# 3_classyTKL_mcu.net
KiCad netlist of a schematic drawn in Altium Designer
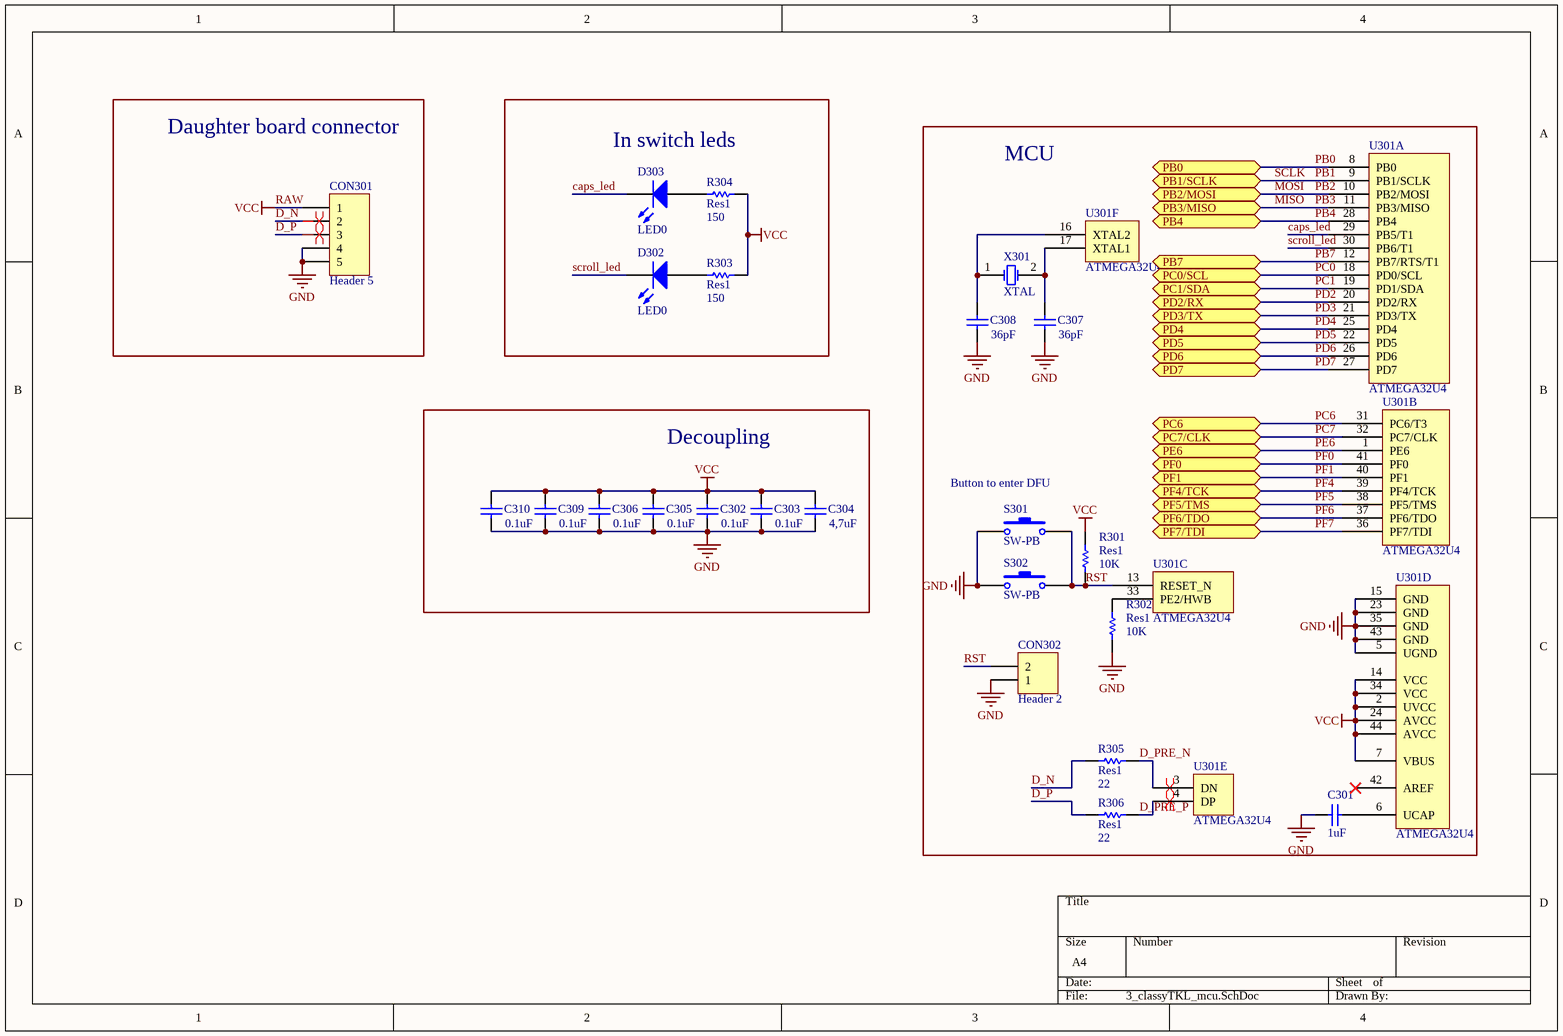
[diagram p0: 3_classyTKL_mcu.SchDoc]

(export (version "E")
  (design (tool "Eeschema 10.0.6"))
  (components
    (comp (ref "C301")
      (value "1uF")
      (footprint "C0603[1608]")
      (description "Capacitor")
      (fields (field (name "MFG") "KEMET") (field (name "LCSC PART #") "C15849"))
      (libsource (lib "Miscellaneous Devices") (part "Cap"))
    )
    (comp (ref "C302")
      (value "0.1uF")
      (footprint "C0603[1608]")
      (description "Capacitor")
      (fields (field (name "MFG") "KEMET") (field (name "LCSC PART #") "C14663"))
      (libsource (lib "Miscellaneous Devices") (part "Cap"))
    )
    (comp (ref "C303")
      (value "0.1uF")
      (footprint "C0603[1608]")
      (description "Capacitor")
      (fields (field (name "MFG") "KEMET") (field (name "LCSC PART #") "C14663"))
      (libsource (lib "Miscellaneous Devices") (part "Cap"))
    )
    (comp (ref "C304")
      (value "4,7uF")
      (footprint "C1206[3216]")
      (description "Capacitor")
      (fields (field (name "MFG") "KEMET") (field (name "LCSC PART #") "C29823"))
      (libsource (lib "Miscellaneous Devices") (part "Cap"))
    )
    (comp (ref "C305")
      (value "0.1uF")
      (footprint "C0603[1608]")
      (description "Capacitor")
      (fields (field (name "MFG") "KEMET") (field (name "LCSC PART #") "C14663"))
      (libsource (lib "Miscellaneous Devices") (part "Cap"))
    )
    (comp (ref "C306")
      (value "0.1uF")
      (footprint "C0603[1608]")
      (description "Capacitor")
      (fields (field (name "MFG") "KEMET") (field (name "LCSC PART #") "C14663"))
      (libsource (lib "Miscellaneous Devices") (part "Cap"))
    )
    (comp (ref "C307")
      (value "36pF")
      (footprint "C0603[1608]")
      (description "Capacitor")
      (fields (field (name "MFG") "KEMET") (field (name "LCSC PART #") "C159790"))
      (libsource (lib "Miscellaneous Devices") (part "Cap"))
    )
    (comp (ref "C308")
      (value "36pF")
      (footprint "C0603[1608]")
      (description "Capacitor")
      (fields (field (name "MFG") "KEMET") (field (name "LCSC PART #") "C159790"))
      (libsource (lib "Miscellaneous Devices") (part "Cap"))
    )
    (comp (ref "C309")
      (value "0.1uF")
      (footprint "C0603[1608]")
      (description "Capacitor")
      (fields (field (name "MFG") "KEMET") (field (name "LCSC PART #") "C14663"))
      (libsource (lib "Miscellaneous Devices") (part "Cap"))
    )
    (comp (ref "C310")
      (value "0.1uF")
      (footprint "C0603[1608]")
      (description "Capacitor")
      (fields (field (name "MFG") "KEMET") (field (name "LCSC PART #") "C14663"))
      (libsource (lib "Miscellaneous Devices") (part "Cap"))
    )
    (comp (ref "CON301")
      (value "Header 5")
      (footprint "JST SM04B-SRSS-TB")
      (description "JST for USB daughter board")
      (fields (field (name "MFG") "JST Sales America Inc.") (field (name "LCSC PART #") "C160404"))
      (libsource (lib "Miscellaneous Connectors") (part "Header 5"))
    )
    (comp (ref "CON302")
      (value "Header 2")
      (footprint "HDR1X2")
      (description "Header, 2-Pin")
      (libsource (lib "Miscellaneous Connectors") (part "Header 2"))
    )
    (comp (ref "D302")
      (value "LED0")
      (footprint "MX-switch - LED")
      (description "Typical INFRARED GaAs LED")
      (libsource (lib "Miscellaneous Devices") (part "LED0"))
    )
    (comp (ref "D303")
      (value "LED0")
      (footprint "MX-switch - CAPS - LED NO SWITCH")
      (description "Typical INFRARED GaAs LED")
      (libsource (lib "Miscellaneous Devices") (part "LED0"))
    )
    (comp (ref "R301")
      (value "Res1")
      (footprint "R0603[1608]")
      (description "Resistor")
      (fields
        (field (name "ALTIUM_VALUE") "10K")
        (field (name "MFG") "Panasonic Electronic Components")
        (field (name "LCSC PART #") "C25804")
      )
      (libsource (lib "Miscellaneous Devices") (part "Res1"))
    )
    (comp (ref "R302")
      (value "Res1")
      (footprint "R0603[1608]")
      (description "Resistor")
      (fields
        (field (name "ALTIUM_VALUE") "10K")
        (field (name "MFG") "Panasonic Electronic Components")
        (field (name "LCSC PART #") "C25804")
      )
      (libsource (lib "Miscellaneous Devices") (part "Res1"))
    )
    (comp (ref "R303")
      (value "Res1")
      (footprint "R0603[1608] - THT")
      (description "Resistor")
      (fields (field (name "ALTIUM_VALUE") "150"))
      (libsource (lib "Miscellaneous Devices") (part "Res1"))
    )
    (comp (ref "R304")
      (value "Res1")
      (footprint "R0603[1608] - THT")
      (description "Resistor")
      (fields (field (name "ALTIUM_VALUE") "150"))
      (libsource (lib "Miscellaneous Devices") (part "Res1"))
    )
    (comp (ref "R305")
      (value "Res1")
      (footprint "R0603[1608]")
      (description "Resistor")
      (fields
        (field (name "ALTIUM_VALUE") "22")
        (field (name "MFG") "Panasonic Electronic Components")
        (field (name "LCSC PART #") "C23345")
      )
      (libsource (lib "Miscellaneous Devices") (part "Res1"))
    )
    (comp (ref "R306")
      (value "Res1")
      (footprint "R0603[1608]")
      (description "Resistor")
      (fields
        (field (name "ALTIUM_VALUE") "22")
        (field (name "MFG") "Panasonic Electronic Components")
        (field (name "LCSC PART #") "C23345")
      )
      (libsource (lib "Miscellaneous Devices") (part "Res1"))
    )
    (comp (ref "S301")
      (value "SW-PB")
      (footprint "Combo switch")
      (description "Switch")
      (fields (field (name "MFG") "C&K") (field (name "LCSC PART #") "C318888"))
      (libsource (lib "Miscellaneous Devices") (part "SW-PB"))
    )
    (comp (ref "S302")
      (value "SW-PB")
      (footprint "Combo switch")
      (description "Switch")
      (fields (field (name "MFG") "C&K") (field (name "LCSC PART #") "C318888"))
      (libsource (lib "Miscellaneous Devices") (part "SW-PB"))
    )
    (comp (ref "U301")
      (value "ATMEGA32U4")
      (footprint "ATMEGA32U4-COMBO")
      (description "MCU")
      (fields
        (field (name "LCSC PART #") "C45874")
        (field (name "MFG") "Microchip Technology")
        (field (name "MRF.PART") "ATMEGA32U4-MUR")
      )
      (libsource (lib "") (part "ATMEGA32U4_1"))
    )
    (comp (ref "X301")
      (value "XTAL")
      (footprint "CTS 445-series crystal")
      (description "Crystal Oscillator")
      (fields (field (name "LCSC PART #") "C112572") (field (name "MRF.PART") "X503216MSB2GI"))
      (libsource (lib "Miscellaneous Devices") (part "XTAL"))
    )
  )
  (nets
    (net (code "1") (name "/D_N") (class "Default")
      (node (ref "CON301") (pin "2") (pinfunction "2_2") (pintype "passive"))
      (node (ref "R305") (pin "2") (pinfunction "2_2") (pintype "passive"))
    )
    (net (code "2") (name "/D_P") (class "Default")
      (node (ref "CON301") (pin "3") (pinfunction "3_3") (pintype "passive"))
      (node (ref "R306") (pin "2") (pinfunction "2_2") (pintype "passive"))
    )
    (net (code "3") (name "/D_PRE_N") (class "Default")
      (node (ref "R305") (pin "1") (pinfunction "1_1") (pintype "passive"))
      (node (ref "U301") (pin "3") (pinfunction "DN_3") (pintype "passive"))
    )
    (net (code "4") (name "/D_PRE_P") (class "Default")
      (node (ref "R306") (pin "1") (pinfunction "1_1") (pintype "passive"))
      (node (ref "U301") (pin "4") (pinfunction "DP_4") (pintype "passive"))
    )
    (net (code "5") (name "/MISO") (class "Default")
      (node (ref "U301") (pin "11") (pinfunction "PB3/MISO_11") (pintype "passive"))
    )
    (net (code "6") (name "/MOSI") (class "Default")
      (node (ref "U301") (pin "10") (pinfunction "PB2/MOSI_10") (pintype "passive"))
    )
    (net (code "7") (name "/PB0") (class "Default")
      (node (ref "U301") (pin "8") (pinfunction "PB0_8") (pintype "passive"))
    )
    (net (code "8") (name "/PB1") (class "Default")
      (node (ref "U301") (pin "9") (pinfunction "PB1/SCLK_9") (pintype "passive"))
    )
    (net (code "9") (name "/PB4") (class "Default")
      (node (ref "U301") (pin "28") (pinfunction "PB4_28") (pintype "passive"))
    )
    (net (code "10") (name "/PB7") (class "Default")
      (node (ref "U301") (pin "12") (pinfunction "PB7/RTS/T1_12") (pintype "passive"))
    )
    (net (code "11") (name "/PC0") (class "Default")
      (node (ref "U301") (pin "18") (pinfunction "PD0/SCL_18") (pintype "passive"))
    )
    (net (code "12") (name "/PC1") (class "Default")
      (node (ref "U301") (pin "19") (pinfunction "PD1/SDA_19") (pintype "passive"))
    )
    (net (code "13") (name "/PC6") (class "Default")
      (node (ref "U301") (pin "31") (pinfunction "PC6/T3_31") (pintype "passive"))
    )
    (net (code "14") (name "/PC7") (class "Default")
      (node (ref "U301") (pin "32") (pinfunction "PC7/CLK_32") (pintype "passive"))
    )
    (net (code "15") (name "/PD2") (class "Default")
      (node (ref "U301") (pin "20") (pinfunction "PD2/RX_20") (pintype "passive"))
    )
    (net (code "16") (name "/PD3") (class "Default")
      (node (ref "U301") (pin "21") (pinfunction "PD3/TX_21") (pintype "passive"))
    )
    (net (code "17") (name "/PD4") (class "Default")
      (node (ref "U301") (pin "25") (pinfunction "PD4_25") (pintype "passive"))
    )
    (net (code "18") (name "/PD5") (class "Default")
      (node (ref "U301") (pin "22") (pinfunction "PD5_22") (pintype "passive"))
    )
    (net (code "19") (name "/PD6") (class "Default")
      (node (ref "U301") (pin "26") (pinfunction "PD6_26") (pintype "passive"))
    )
    (net (code "20") (name "/PD7") (class "Default")
      (node (ref "U301") (pin "27") (pinfunction "PD7_27") (pintype "passive"))
    )
    (net (code "21") (name "/PE6") (class "Default")
      (node (ref "U301") (pin "1") (pinfunction "PE6_1") (pintype "passive"))
    )
    (net (code "22") (name "/PF0") (class "Default")
      (node (ref "U301") (pin "41") (pinfunction "PF0_41") (pintype "passive"))
    )
    (net (code "23") (name "/PF1") (class "Default")
      (node (ref "U301") (pin "40") (pinfunction "PF1_40") (pintype "passive"))
    )
    (net (code "24") (name "/PF4") (class "Default")
      (node (ref "U301") (pin "39") (pinfunction "PF4/TCK_39") (pintype "passive"))
    )
    (net (code "25") (name "/PF5") (class "Default")
      (node (ref "U301") (pin "38") (pinfunction "PF5/TMS_38") (pintype "passive"))
    )
    (net (code "26") (name "/PF6") (class "Default")
      (node (ref "U301") (pin "37") (pinfunction "PF6/TDO_37") (pintype "passive"))
    )
    (net (code "27") (name "/PF7") (class "Default")
      (node (ref "U301") (pin "36") (pinfunction "PF7/TDI_36") (pintype "passive"))
    )
    (net (code "28") (name "/RST") (class "Default")
      (node (ref "CON302") (pin "2") (pinfunction "2_2") (pintype "passive"))
      (node (ref "R301") (pin "2") (pinfunction "2_2") (pintype "passive"))
      (node (ref "S301") (pin "2") (pinfunction "2_2") (pintype "passive"))
      (node (ref "S302") (pin "2") (pinfunction "2_2") (pintype "passive"))
      (node (ref "U301") (pin "13") (pinfunction "RESET_N_13") (pintype "passive"))
    )
    (net (code "29") (name "/caps_led") (class "Default")
      (node (ref "D303") (pin "2") (pinfunction "K_2") (pintype "passive"))
      (node (ref "U301") (pin "29") (pinfunction "PB5/T1_29") (pintype "passive"))
    )
    (net (code "30") (name "/scroll_led") (class "Default")
      (node (ref "D302") (pin "2") (pinfunction "K_2") (pintype "passive"))
      (node (ref "U301") (pin "30") (pinfunction "PB6/T1_30") (pintype "passive"))
    )
    (net (code "31") (name "GND") (class "Default")
      (node (ref "C301") (pin "1") (pinfunction "1_1") (pintype "passive"))
      (node (ref "C302") (pin "1") (pinfunction "1_1") (pintype "passive"))
      (node (ref "C303") (pin "1") (pinfunction "1_1") (pintype "passive"))
      (node (ref "C304") (pin "1") (pinfunction "1_1") (pintype "passive"))
      (node (ref "C305") (pin "1") (pinfunction "1_1") (pintype "passive"))
      (node (ref "C306") (pin "1") (pinfunction "1_1") (pintype "passive"))
      (node (ref "C307") (pin "1") (pinfunction "1_1") (pintype "passive"))
      (node (ref "C308") (pin "1") (pinfunction "1_1") (pintype "passive"))
      (node (ref "C309") (pin "1") (pinfunction "1_1") (pintype "passive"))
      (node (ref "C310") (pin "1") (pinfunction "1_1") (pintype "passive"))
      (node (ref "CON301") (pin "4") (pinfunction "4_4") (pintype "passive"))
      (node (ref "CON301") (pin "5") (pinfunction "5_5") (pintype "passive"))
      (node (ref "CON302") (pin "1") (pinfunction "1_1") (pintype "passive"))
      (node (ref "R302") (pin "2") (pinfunction "2_2") (pintype "passive"))
      (node (ref "S301") (pin "1") (pinfunction "1_1") (pintype "passive"))
      (node (ref "S302") (pin "1") (pinfunction "1_1") (pintype "passive"))
      (node (ref "U301") (pin "15") (pinfunction "GND_15") (pintype "passive"))
      (node (ref "U301") (pin "23") (pinfunction "GND_23") (pintype "passive"))
      (node (ref "U301") (pin "35") (pinfunction "GND_35") (pintype "passive"))
      (node (ref "U301") (pin "43") (pinfunction "GND_43") (pintype "passive"))
      (node (ref "U301") (pin "5") (pinfunction "UGND_5") (pintype "passive"))
    )
    (net (code "32") (name "Net-(D302-A)") (class "Default")
      (node (ref "D302") (pin "1") (pinfunction "A_1") (pintype "passive"))
      (node (ref "R303") (pin "2") (pinfunction "2_2") (pintype "passive"))
    )
    (net (code "33") (name "Net-(D303-A)") (class "Default")
      (node (ref "D303") (pin "1") (pinfunction "A_1") (pintype "passive"))
      (node (ref "R304") (pin "2") (pinfunction "2_2") (pintype "passive"))
    )
    (net (code "34") (name "Net-(U301C-PE2{slash}HWB)") (class "Default")
      (node (ref "R302") (pin "1") (pinfunction "1_1") (pintype "passive"))
      (node (ref "U301") (pin "33") (pinfunction "PE2/HWB_33") (pintype "passive"))
    )
    (net (code "35") (name "Net-(U301D-UCAP)") (class "Default")
      (node (ref "C301") (pin "2") (pinfunction "2_2") (pintype "passive"))
      (node (ref "U301") (pin "6") (pinfunction "UCAP_6") (pintype "passive"))
    )
    (net (code "36") (name "Net-(U301F-XTAL1)") (class "Default")
      (node (ref "C307") (pin "2") (pinfunction "2_2") (pintype "passive"))
      (node (ref "U301") (pin "17") (pinfunction "XTAL1_17") (pintype "passive"))
      (node (ref "X301") (pin "2") (pinfunction "OSC2_2") (pintype "passive"))
    )
    (net (code "37") (name "Net-(U301F-XTAL2)") (class "Default")
      (node (ref "C308") (pin "2") (pinfunction "2_2") (pintype "passive"))
      (node (ref "U301") (pin "16") (pinfunction "XTAL2_16") (pintype "passive"))
      (node (ref "X301") (pin "1") (pinfunction "OSC1_1") (pintype "passive"))
    )
    (net (code "38") (name "VCC") (class "Default")
      (node (ref "C302") (pin "2") (pinfunction "2_2") (pintype "passive"))
      (node (ref "C303") (pin "2") (pinfunction "2_2") (pintype "passive"))
      (node (ref "C304") (pin "2") (pinfunction "2_2") (pintype "passive"))
      (node (ref "C305") (pin "2") (pinfunction "2_2") (pintype "passive"))
      (node (ref "C306") (pin "2") (pinfunction "2_2") (pintype "passive"))
      (node (ref "C309") (pin "2") (pinfunction "2_2") (pintype "passive"))
      (node (ref "C310") (pin "2") (pinfunction "2_2") (pintype "passive"))
      (node (ref "CON301") (pin "1") (pinfunction "1_1") (pintype "passive"))
      (node (ref "R301") (pin "1") (pinfunction "1_1") (pintype "passive"))
      (node (ref "R303") (pin "1") (pinfunction "1_1") (pintype "passive"))
      (node (ref "R304") (pin "1") (pinfunction "1_1") (pintype "passive"))
      (node (ref "U301") (pin "14") (pinfunction "VCC_14") (pintype "passive"))
      (node (ref "U301") (pin "2") (pinfunction "UVCC_2") (pintype "passive"))
      (node (ref "U301") (pin "24") (pinfunction "AVCC_24") (pintype "passive"))
      (node (ref "U301") (pin "34") (pinfunction "VCC_34") (pintype "passive"))
      (node (ref "U301") (pin "44") (pinfunction "AVCC_44") (pintype "passive"))
      (node (ref "U301") (pin "7") (pinfunction "VBUS_7") (pintype "passive"))
    )
    (net (code "39") (name "unconnected-(U301D-AREF-Pad42)") (class "Default")
      (node (ref "U301") (pin "42") (pinfunction "AREF_42") (pintype "passive+no_connect"))
    )
  )
)
